# fonte_schema.net
KiCad netlist of a schematic drawn in EAGLE
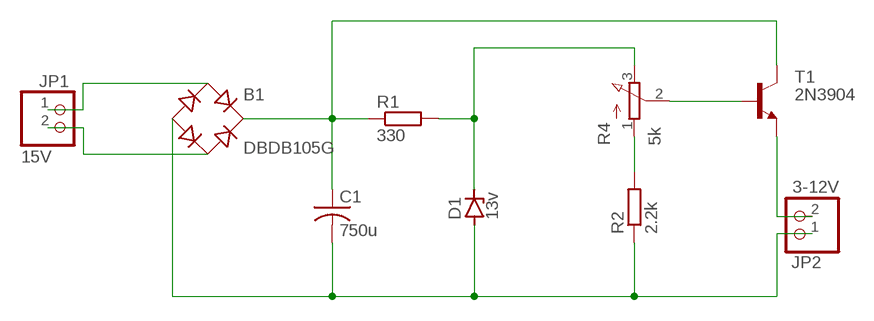
[diagram p0: schematic, sheet 1]

(export (version "E")
  (design (tool "Eeschema 10.0.6"))
  (components
    (comp (ref "B1")
      (value "DBDB105G")
      (footprint "eagle-import:DB")
      (libsource (lib "eagle-import") (part "DB?GDB105"))
    )
    (comp (ref "C1")
      (value "750u")
      (footprint "eagle-import:C025-025X050")
      (libsource (lib "eagle-import") (part "C-US025-025X050"))
    )
    (comp (ref "D1")
      (value "13v")
      (footprint "eagle-import:SOD81")
      (fields (field (name "SPICEPREFIX") "D"))
      (libsource (lib "eagle-import") (part "BZD23"))
    )
    (comp (ref "JP1")
      (value "15V")
      (footprint "eagle-import:1X02")
      (fields (field (name "SPICEPREFIX") "H"))
      (libsource (lib "eagle-import") (part "PINHD-1X2"))
    )
    (comp (ref "JP2")
      (value "3-12V")
      (footprint "eagle-import:1X02")
      (fields (field (name "SPICEPREFIX") "H"))
      (libsource (lib "eagle-import") (part "PINHD-1X2"))
    )
    (comp (ref "R1")
      (value "330")
      (footprint "eagle-import:0204_7")
      (libsource (lib "eagle-import") (part "R-EU_0204/7"))
    )
    (comp (ref "R2")
      (value "2.2k")
      (footprint "eagle-import:0204_7")
      (libsource (lib "eagle-import") (part "R-EU_0204/7"))
    )
    (comp (ref "R4")
      (value "5k")
      (footprint "eagle-import:3RP_1610N")
      (fields (field (name "SPICEPREFIX") "J"))
      (libsource (lib "eagle-import") (part "3RP/1610N"))
    )
    (comp (ref "T1")
      (value "2N3904")
      (footprint "eagle-import:TO92")
      (fields (field (name "SPICEPREFIX") "J"))
      (libsource (lib "eagle-import") (part "2N3904"))
    )
  )
  (nets
    (net (code "1") (name "Net-(B1-Pad-)") (class "Default")
      (node (ref "B1") (pin "-") (pinfunction "-_-") (pintype "passive"))
      (node (ref "C1") (pin "2") (pinfunction "2_2") (pintype "passive"))
      (node (ref "D1") (pin "A") (pinfunction "A_A") (pintype "passive"))
      (node (ref "JP2") (pin "1") (pinfunction "1_1") (pintype "passive"))
      (node (ref "R2") (pin "1") (pinfunction "1_1") (pintype "passive"))
    )
    (net (code "2") (name "Net-(B1-PadAC1)") (class "Default")
      (node (ref "B1") (pin "AC1") (pinfunction "AC1_AC1") (pintype "passive"))
      (node (ref "JP1") (pin "1") (pinfunction "1_1") (pintype "passive"))
    )
    (net (code "3") (name "Net-(B1-PadAC2)") (class "Default")
      (node (ref "B1") (pin "AC2") (pinfunction "AC2_AC2") (pintype "passive"))
      (node (ref "JP1") (pin "2") (pinfunction "2_2") (pintype "passive"))
    )
    (net (code "4") (name "Net-(R4-A)") (class "Default")
      (node (ref "R2") (pin "2") (pinfunction "2_2") (pintype "passive"))
      (node (ref "R4") (pin "1") (pinfunction "A_1") (pintype "passive"))
    )
    (net (code "5") (name "Net-(R4-E)") (class "Default")
      (node (ref "D1") (pin "C") (pinfunction "C_C") (pintype "passive"))
      (node (ref "R1") (pin "2") (pinfunction "2_2") (pintype "passive"))
      (node (ref "R4") (pin "3") (pinfunction "E_3") (pintype "passive"))
    )
    (net (code "6") (name "Net-(R4-S)") (class "Default")
      (node (ref "R4") (pin "2") (pinfunction "S_2") (pintype "passive"))
      (node (ref "T1") (pin "2") (pinfunction "B_2") (pintype "passive"))
    )
    (net (code "7") (name "Net-(T1-C)") (class "Default")
      (node (ref "B1") (pin "+") (pinfunction "+_+") (pintype "passive"))
      (node (ref "C1") (pin "1") (pinfunction "1_1") (pintype "passive"))
      (node (ref "R1") (pin "1") (pinfunction "1_1") (pintype "passive"))
      (node (ref "T1") (pin "1") (pinfunction "C_1") (pintype "passive"))
    )
    (net (code "8") (name "Net-(T1-E)") (class "Default")
      (node (ref "JP2") (pin "2") (pinfunction "2_2") (pintype "passive"))
      (node (ref "T1") (pin "3") (pinfunction "E_3") (pintype "passive"))
    )
  )
)
